# Esquematico.net
KiCad netlist of a schematic drawn in Altium Designer
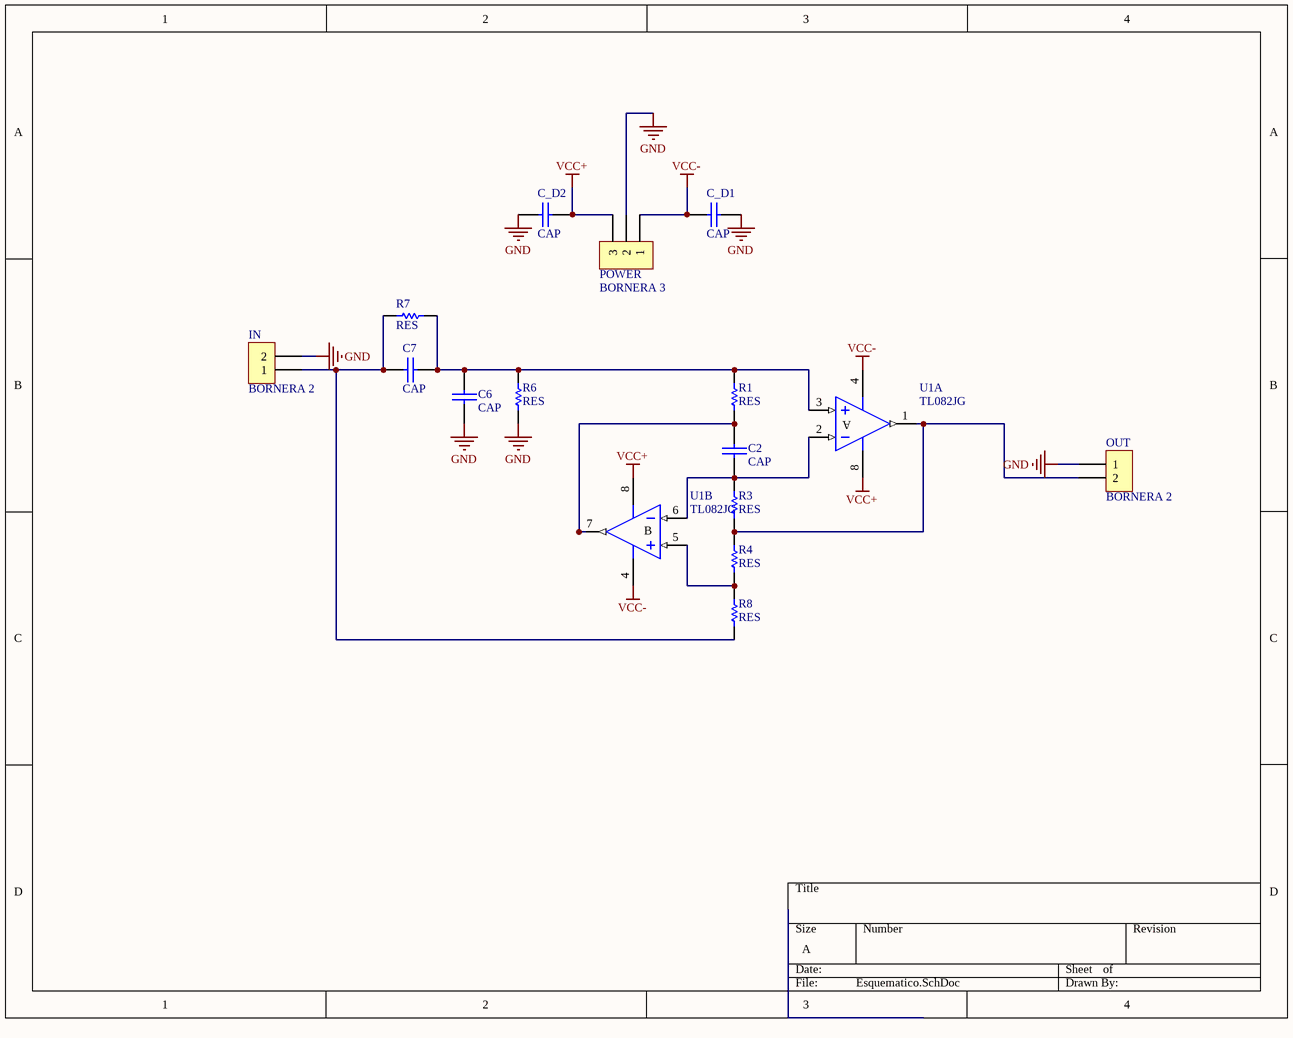
[diagram p0: Esquematico.SchDoc]

(export (version "E")
  (design (tool "Eeschema 10.0.6"))
  (components
    (comp (ref "C2") (value "CAP") (footprint "CAP200") (libsource (lib "LIB PIO IX") (part "CAP")))
    (comp (ref "C6") (value "CAP") (footprint "CAP200") (libsource (lib "LIB PIO IX") (part "CAP")))
    (comp (ref "C7") (value "CAP") (footprint "CAP200") (libsource (lib "LIB PIO IX") (part "CAP")))
    (comp (ref "C_D1") (value "CAP") (footprint "0805") (libsource (lib "LIB PIO IX") (part "CAP")))
    (comp (ref "C_D2") (value "CAP") (footprint "0805") (libsource (lib "LIB PIO IX") (part "CAP")))
    (comp (ref "IN")
      (value "BORNERA 2")
      (footprint "BORNERA2")
      (libsource (lib "LIB PIO IX") (part "BORNERA 2"))
    )
    (comp (ref "OUT") (value "BORNERA 2") (footprint "BORNERA2") (libsource (lib "") (part "BORNERA 2_1")))
    (comp (ref "POWER")
      (value "BORNERA 3")
      (footprint "BORNERA3")
      (libsource (lib "LIB PIO IX") (part "BORNERA 3"))
    )
    (comp (ref "R1") (value "RES") (footprint "RES300") (libsource (lib "LIB PIO IX") (part "RES")))
    (comp (ref "R3") (value "RES") (footprint "RES300") (libsource (lib "LIB PIO IX") (part "RES")))
    (comp (ref "R4") (value "RES") (footprint "RES300") (libsource (lib "LIB PIO IX") (part "RES")))
    (comp (ref "R6") (value "RES") (footprint "RES300") (libsource (lib "LIB PIO IX") (part "RES")))
    (comp (ref "R7") (value "RES") (footprint "RES300") (libsource (lib "LIB PIO IX") (part "RES")))
    (comp (ref "R8") (value "RES") (footprint "RES300") (libsource (lib "LIB PIO IX") (part "RES")))
    (comp (ref "U1")
      (value "TL082JG")
      (footprint "JG008")
      (description "JFET-Input Operational Amplifier")
      (fields (field (name "PUBLISHER") "Altium Limited"))
      (libsource (lib "TI Operational Amplifier") (part "TL082JG"))
    )
  )
  (nets
    (net (code "1") (name "GND") (class "Default")
      (node (ref "C6") (pin "1") (pinfunction "1_1") (pintype "passive"))
      (node (ref "C_D1") (pin "2") (pinfunction "2_2") (pintype "passive"))
      (node (ref "C_D2") (pin "1") (pinfunction "1_1") (pintype "passive"))
      (node (ref "IN") (pin "2") (pinfunction "2_2") (pintype "passive"))
      (node (ref "OUT") (pin "1") (pinfunction "1_1") (pintype "passive"))
      (node (ref "POWER") (pin "2") (pinfunction "2_2") (pintype "passive"))
      (node (ref "R6") (pin "1") (pinfunction "1_1") (pintype "passive"))
    )
    (net (code "2") (name "Net-(C7-Pad1)") (class "Default")
      (node (ref "C7") (pin "1") (pinfunction "1_1") (pintype "passive"))
      (node (ref "IN") (pin "1") (pinfunction "1_1") (pintype "passive"))
      (node (ref "R7") (pin "1") (pinfunction "1_1") (pintype "passive"))
      (node (ref "R8") (pin "1") (pinfunction "1_1") (pintype "passive"))
    )
    (net (code "3") (name "Net-(U1A-IN+)") (class "Default")
      (node (ref "C6") (pin "2") (pinfunction "2_2") (pintype "passive"))
      (node (ref "C7") (pin "2") (pinfunction "2_2") (pintype "passive"))
      (node (ref "R1") (pin "2") (pinfunction "2_2") (pintype "passive"))
      (node (ref "R6") (pin "2") (pinfunction "2_2") (pintype "passive"))
      (node (ref "R7") (pin "2") (pinfunction "2_2") (pintype "passive"))
      (node (ref "U1") (pin "3") (pinfunction "IN+_3") (pintype "input"))
    )
    (net (code "4") (name "Net-(U1A-IN-)") (class "Default")
      (node (ref "C2") (pin "2") (pinfunction "2_2") (pintype "passive"))
      (node (ref "R3") (pin "2") (pinfunction "2_2") (pintype "passive"))
      (node (ref "U1") (pin "2") (pinfunction "IN-_2") (pintype "input"))
      (node (ref "U1") (pin "6") (pinfunction "IN-_6") (pintype "input"))
    )
    (net (code "5") (name "Net-(U1A-OUT)") (class "Default")
      (node (ref "OUT") (pin "2") (pinfunction "2_2") (pintype "passive"))
      (node (ref "R3") (pin "1") (pinfunction "1_1") (pintype "passive"))
      (node (ref "R4") (pin "2") (pinfunction "2_2") (pintype "passive"))
      (node (ref "U1") (pin "1") (pinfunction "OUT_1") (pintype "output"))
    )
    (net (code "6") (name "Net-(U1B-IN+)") (class "Default")
      (node (ref "R4") (pin "1") (pinfunction "1_1") (pintype "passive"))
      (node (ref "R8") (pin "2") (pinfunction "2_2") (pintype "passive"))
      (node (ref "U1") (pin "5") (pinfunction "IN+_5") (pintype "input"))
    )
    (net (code "7") (name "Net-(U1B-OUT)") (class "Default")
      (node (ref "C2") (pin "1") (pinfunction "1_1") (pintype "passive"))
      (node (ref "R1") (pin "1") (pinfunction "1_1") (pintype "passive"))
      (node (ref "U1") (pin "7") (pinfunction "OUT_7") (pintype "output"))
    )
    (net (code "8") (name "VCC+") (class "Default")
      (node (ref "C_D2") (pin "2") (pinfunction "2_2") (pintype "passive"))
      (node (ref "POWER") (pin "3") (pinfunction "3_3") (pintype "passive"))
      (node (ref "U1") (pin "8") (pinfunction "V+_8") (pintype "power_in"))
    )
    (net (code "9") (name "VCC-") (class "Default")
      (node (ref "C_D1") (pin "1") (pinfunction "1_1") (pintype "passive"))
      (node (ref "POWER") (pin "1") (pinfunction "1_1") (pintype "passive"))
      (node (ref "U1") (pin "4") (pinfunction "V-_4") (pintype "power_in"))
    )
  )
)
